# usbhub.net
KiCad netlist of a schematic drawn in Altium Designer
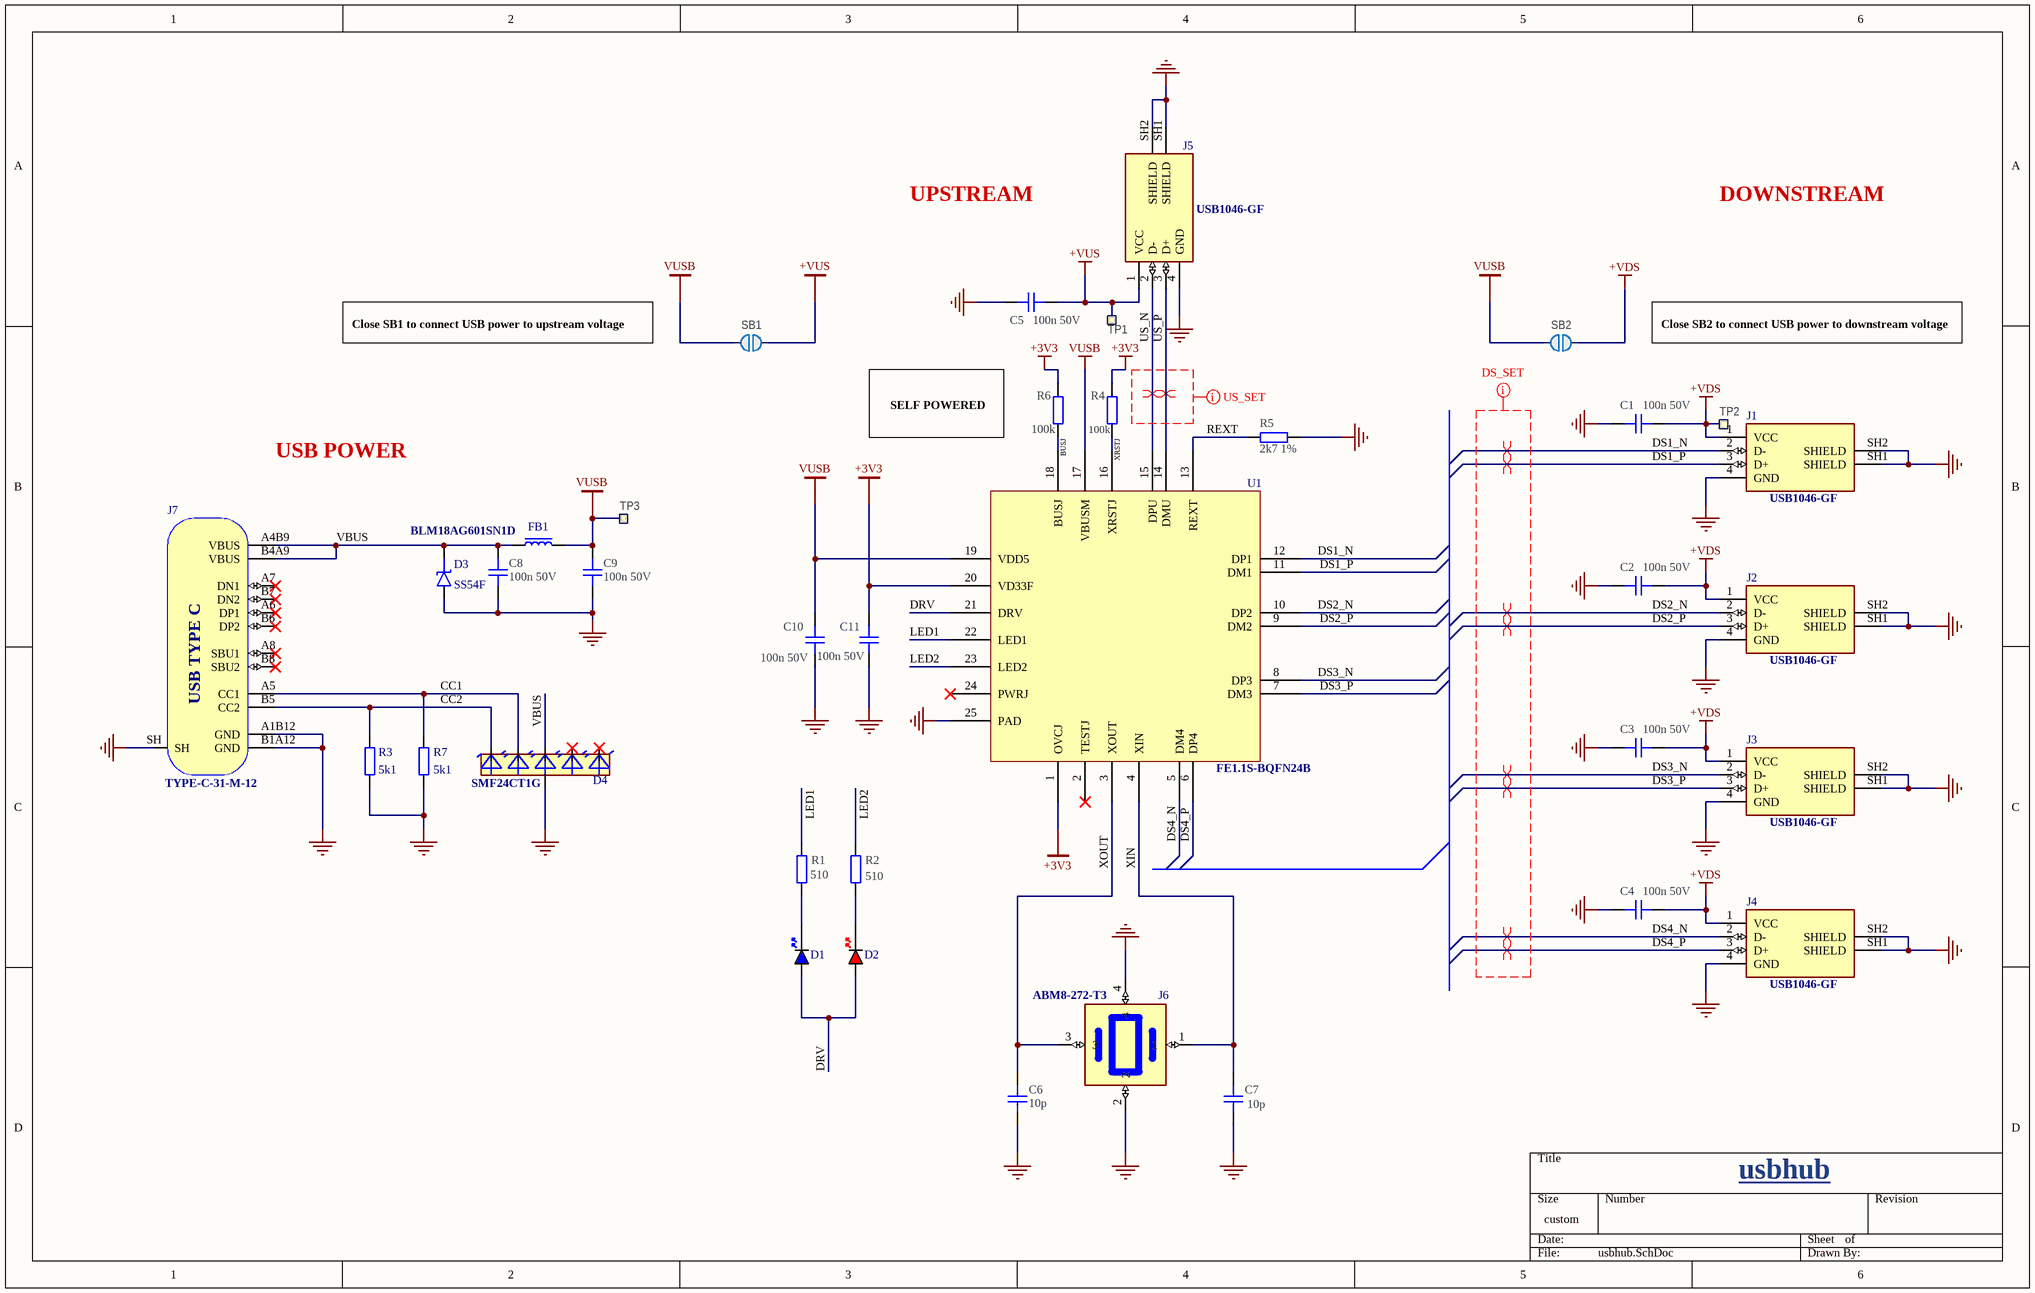
[diagram p0: usbhub.SchDoc]

(export (version "E")
  (design (tool "Eeschema 10.0.6"))
  (components
    (comp (ref "C1")
      (value "100n 50V")
      (footprint "CAPC1005X04L")
      (description "Capacitor, X5R, ±20%")
      (fields
        (field (name "PART NUMBER") "C0402-4µ7")
        (field (name "MANUFACTURER") "N.A.")
        (field (name "AUTHOR") "rsk")
      )
      (libsource (lib "Sch_Lib") (part "C0402-4µ7"))
    )
    (comp (ref "C2")
      (value "100n 50V")
      (footprint "CAPC1005X04L")
      (description "Capacitor, X5R, ±20%")
      (fields
        (field (name "PART NUMBER") "C0402-4µ7")
        (field (name "MANUFACTURER") "N.A.")
        (field (name "AUTHOR") "rsk")
      )
      (libsource (lib "Sch_Lib") (part "C0402-4µ7"))
    )
    (comp (ref "C3")
      (value "100n 50V")
      (footprint "CAPC1005X04L")
      (description "Capacitor, X5R, ±20%")
      (fields
        (field (name "PART NUMBER") "C0402-4µ7")
        (field (name "MANUFACTURER") "N.A.")
        (field (name "AUTHOR") "rsk")
      )
      (libsource (lib "Sch_Lib") (part "C0402-4µ7"))
    )
    (comp (ref "C4")
      (value "100n 50V")
      (footprint "CAPC1005X04L")
      (description "Capacitor, X5R, ±20%")
      (fields
        (field (name "PART NUMBER") "C0402-4µ7")
        (field (name "MANUFACTURER") "N.A.")
        (field (name "AUTHOR") "rsk")
      )
      (libsource (lib "Sch_Lib") (part "C0402-4µ7"))
    )
    (comp (ref "C5")
      (value "100n 50V")
      (footprint "CAPC1005X04L")
      (description "Capacitor, X5R, ±20%")
      (fields
        (field (name "PART NUMBER") "C0402-4µ7")
        (field (name "MANUFACTURER") "N.A.")
        (field (name "AUTHOR") "rsk")
      )
      (libsource (lib "Sch_Lib") (part "C0402-4µ7"))
    )
    (comp (ref "C6")
      (value "10p")
      (footprint "CAPC1005X04L")
      (description "Capacitor, X5R, ±20%")
      (fields
        (field (name "PART NUMBER") "C0402-4µ7")
        (field (name "MANUFACTURER") "N.A.")
        (field (name "AUTHOR") "rsk")
      )
      (libsource (lib "Sch_Lib") (part "C0402-4µ7"))
    )
    (comp (ref "C7")
      (value "10p")
      (footprint "CAPC1005X04L")
      (description "Capacitor, X5R, ±20%")
      (fields
        (field (name "PART NUMBER") "C0402-4µ7")
        (field (name "MANUFACTURER") "N.A.")
        (field (name "AUTHOR") "rsk")
      )
      (libsource (lib "Sch_Lib") (part "C0402-4µ7"))
    )
    (comp (ref "C8")
      (value "100n 50V")
      (footprint "CAPC1005X04L")
      (description "Capacitor, X5R, ±20%")
      (fields
        (field (name "PART NUMBER") "C0402-4µ7")
        (field (name "MANUFACTURER") "N.A.")
        (field (name "AUTHOR") "rsk")
      )
      (libsource (lib "Sch_Lib") (part "C0402-4µ7"))
    )
    (comp (ref "C9")
      (value "100n 50V")
      (footprint "CAPC1005X04L")
      (description "Capacitor, X5R, ±20%")
      (fields
        (field (name "PART NUMBER") "C0402-4µ7")
        (field (name "MANUFACTURER") "N.A.")
        (field (name "AUTHOR") "rsk")
      )
      (libsource (lib "Sch_Lib") (part "C0402-4µ7"))
    )
    (comp (ref "C10")
      (value "100n 50V")
      (footprint "CAPC1005X04L")
      (description "Capacitor, X5R, ±20%")
      (fields
        (field (name "PART NUMBER") "C0402-4µ7")
        (field (name "MANUFACTURER") "N.A.")
        (field (name "AUTHOR") "rsk")
      )
      (libsource (lib "Sch_Lib") (part "C0402-4µ7"))
    )
    (comp (ref "C11")
      (value "100n 50V")
      (footprint "CAPC1005X04L")
      (description "Capacitor, X5R, ±20%")
      (fields
        (field (name "PART NUMBER") "C0402-4µ7")
        (field (name "MANUFACTURER") "N.A.")
        (field (name "AUTHOR") "rsk")
      )
      (libsource (lib "Sch_Lib") (part "C0402-4µ7"))
    )
    (comp (ref "D1")
      (value "BLUE")
      (footprint "LED_0402_BLUE")
      (description "LED 0402 BLUE SMD")
      (libsource (lib "Sch_Lib") (part "LED_0402_BLUE"))
    )
    (comp (ref "D2")
      (value "RED")
      (footprint "LED_0402_RED")
      (description "LED 0402 RED SMD")
      (libsource (lib "Sch_Lib") (part "LED_0402_RED"))
    )
    (comp (ref "D3")
      (value "SS54F")
      (footprint "DIOM5226X100N")
      (description "Schottky Diode SMD SMAF package")
      (libsource (lib "Schematic-Lib-PhilsLab") (part "Schottky Diode_3"))
    )
    (comp (ref "D4")
      (value "SMF24CT1G")
      (footprint "SOT65P210X110-6N")
      (description "Quint Uni-Directional TVS Diode, 100W, 6-Pin SC-88 ¦ ON Semiconductor SMF24CT1G")
      (fields (field (name "MP") "SMF05C") (field (name "MF") "ProTek Devices"))
      (libsource (lib "Sch_Lib") (part "SMF24CT1G"))
    )
    (comp (ref "FB1")
      (value "BLM18AG601SN1D")
      (footprint "FB_0603")
      (description "Ferrite Bead SMD 0603")
      (libsource (lib "Sch_Lib") (part "FB_0603"))
    )
    (comp (ref "J1")
      (value "USB1046-GF")
      (footprint "GCT_USB1046-GF-0190-L-B-A_REVB4")
      (description "USB-A (USB TYPE-A) USB 2.0 Receptacle Connector 4 Position Surface Mount, Through Hole")
      (fields (field (name "MF") "Global Connector Technology") (field (name "MP") "USB1046-GF-0190-L-B-A"))
      (libsource (lib "Sch_Lib") (part "USB1046-GF-0190-L-B-A_REVB4"))
    )
    (comp (ref "J2")
      (value "USB1046-GF")
      (footprint "GCT_USB1046-GF-0190-L-B-A_REVB4")
      (description "USB-A (USB TYPE-A) USB 2.0 Receptacle Connector 4 Position Surface Mount, Through Hole")
      (fields (field (name "MF") "Global Connector Technology") (field (name "MP") "USB1046-GF-0190-L-B-A"))
      (libsource (lib "Sch_Lib") (part "USB1046-GF-0190-L-B-A_REVB4"))
    )
    (comp (ref "J3")
      (value "USB1046-GF")
      (footprint "GCT_USB1046-GF-0190-L-B-A_REVB4")
      (description "USB-A (USB TYPE-A) USB 2.0 Receptacle Connector 4 Position Surface Mount, Through Hole")
      (fields (field (name "MF") "Global Connector Technology") (field (name "MP") "USB1046-GF-0190-L-B-A"))
      (libsource (lib "Sch_Lib") (part "USB1046-GF-0190-L-B-A_REVB4"))
    )
    (comp (ref "J4")
      (value "USB1046-GF")
      (footprint "GCT_USB1046-GF-0190-L-B-A_REVB4")
      (description "USB-A (USB TYPE-A) USB 2.0 Receptacle Connector 4 Position Surface Mount, Through Hole")
      (fields (field (name "MF") "Global Connector Technology") (field (name "MP") "USB1046-GF-0190-L-B-A"))
      (libsource (lib "Sch_Lib") (part "USB1046-GF-0190-L-B-A_REVB4"))
    )
    (comp (ref "J5")
      (value "USB1046-GF")
      (footprint "GCT_USB1046-GF-0190-L-B-A_REVB4")
      (description "USB-A (USB TYPE-A) USB 2.0 Receptacle Connector 4 Position Surface Mount, Through Hole")
      (fields (field (name "MF") "Global Connector Technology") (field (name "MP") "USB1046-GF-0190-L-B-A"))
      (libsource (lib "") (part "USB1046-GF-0190-L-B-A_REVB4_1"))
    )
    (comp (ref "J6")
      (value "ABM8-272-T3")
      (footprint "ABM8-272-T3")
      (description "12 MHz Â±30ppm Crystal 10pF 50 Ohms 4-SMD, No Lead")
      (fields (field (name "MF") "ABRACON"))
      (libsource (lib "Sch_Lib") (part "ABM8-272-T3"))
    )
    (comp (ref "J7")
      (value "TYPE-C-31-M-12")
      (footprint "TYPE-C-31-M-12")
      (description "USB Type C Connector Horizontal SMT")
      (fields (field (name "MANUFACTURER") "Koren Hroparts"))
      (libsource (lib "Sch_Lib") (part "TYPE-C-31-M-12"))
    )
    (comp (ref "R1")
      (value "510")
      (footprint "RESC1005X04L")
      (description "Resistor, ±5%, 0.063W")
      (fields
        (field (name "PART NUMBER") "R0402-0R")
        (field (name "MANUFACTURER") "N.A.")
        (field (name "AUTHOR") "rsk")
      )
      (libsource (lib "Sch_Lib") (part "R0402-0R"))
    )
    (comp (ref "R2")
      (value "510")
      (footprint "RESC1005X04L")
      (description "Resistor, ±5%, 0.063W")
      (fields
        (field (name "PART NUMBER") "R0402-0R")
        (field (name "MANUFACTURER") "N.A.")
        (field (name "AUTHOR") "rsk")
      )
      (libsource (lib "Sch_Lib") (part "R0402-0R"))
    )
    (comp (ref "R3")
      (value "5k1")
      (footprint "RES_0603")
      (description "Resistor SMD 0603")
      (libsource (lib "Schematic-Lib-PhilsLab") (part "RES_0603"))
    )
    (comp (ref "R4")
      (value "100k")
      (footprint "RESC1005X04L")
      (description "Resistor, ±5%, 0.063W")
      (fields
        (field (name "PART NUMBER") "R0402-0R")
        (field (name "MANUFACTURER") "N.A.")
        (field (name "AUTHOR") "rsk")
      )
      (libsource (lib "Sch_Lib") (part "R0402-0R"))
    )
    (comp (ref "R5")
      (value "2k7 1%")
      (footprint "RESC1005X04L")
      (description "Resistor, ±5%, 0.063W")
      (fields
        (field (name "PART NUMBER") "R0402-0R")
        (field (name "MANUFACTURER") "N.A.")
        (field (name "AUTHOR") "rsk")
      )
      (libsource (lib "Sch_Lib") (part "R0402-0R"))
    )
    (comp (ref "R6")
      (value "100k")
      (footprint "RESC1005X04L")
      (description "Resistor, ±5%, 0.063W")
      (fields
        (field (name "PART NUMBER") "R0402-0R")
        (field (name "MANUFACTURER") "N.A.")
        (field (name "AUTHOR") "rsk")
      )
      (libsource (lib "Sch_Lib") (part "R0402-0R"))
    )
    (comp (ref "R7")
      (value "5k1")
      (footprint "RES_0603")
      (description "Resistor SMD 0603")
      (libsource (lib "Schematic-Lib-PhilsLab") (part "RES_0603"))
    )
    (comp (ref "SB1")
      (value "Solderbridge")
      (footprint "Solderbridge")
      (fields (field (name "MANUFACTURER") "N.A.") (field (name "AUTHOR") "rsk"))
      (libsource (lib "Sch_Lib") (part "Solderbridge"))
    )
    (comp (ref "SB2")
      (value "Solderbridge")
      (footprint "Solderbridge")
      (fields (field (name "MANUFACTURER") "N.A.") (field (name "AUTHOR") "rsk"))
      (libsource (lib "Sch_Lib") (part "Solderbridge"))
    )
    (comp (ref "TP1")
      (value "Ø1.0mm,SMD")
      (footprint "TP_SMD_D1.0mm")
      (description "1.0mm circular SMD testpad")
      (fields
        (field (name "PART NUMBER") "TP_SMD_Ø1.0MM")
        (field (name "MANUFACTURER") "Nordic Semiconductor")
        (field (name "AUTHOR") "rsk")
      )
      (libsource (lib "") (part "TP_SMD_Ø1.0MM_1"))
    )
    (comp (ref "TP2")
      (value "Ø1.0mm,SMD")
      (footprint "TP_SMD_D1.0mm")
      (description "1.0mm circular SMD testpad")
      (fields
        (field (name "PART NUMBER") "TP_SMD_Ø1.0MM")
        (field (name "MANUFACTURER") "Nordic Semiconductor")
        (field (name "AUTHOR") "rsk")
      )
      (libsource (lib "Sch_Lib") (part "TP_SMD_Ø1.0MM"))
    )
    (comp (ref "TP3")
      (value "Ø1.0mm,SMD")
      (footprint "TP_SMD_D1.0mm")
      (description "1.0mm circular SMD testpad")
      (fields
        (field (name "PART NUMBER") "TP_SMD_Ø1.0MM")
        (field (name "MANUFACTURER") "Nordic Semiconductor")
        (field (name "AUTHOR") "rsk")
      )
      (libsource (lib "Sch_Lib") (part "TP_SMD_Ø1.0MM"))
    )
    (comp (ref "U1")
      (value "FE1.1S-BQFN24B")
      (footprint "QFN50P400X400X80-25N")
      (description "USB Hub USB 2.0 WQFN-24 Interface Controllers RoHS")
      (libsource (lib "Sch_Lib") (part "FE1.1S-BQFN24B"))
    )
  )
  (nets
    (net (code "1") (name "+3V3") (class "Default")
      (node (ref "C11") (pin "2") (pinfunction "2_2") (pintype "passive"))
      (node (ref "R4") (pin "2") (pinfunction "2_2") (pintype "passive"))
      (node (ref "R6") (pin "2") (pinfunction "2_2") (pintype "passive"))
      (node (ref "U1") (pin "1") (pinfunction "OVCJ_1") (pintype "passive"))
      (node (ref "U1") (pin "20") (pinfunction "VD33F_20") (pintype "passive"))
    )
    (net (code "2") (name "+VDS") (class "Default")
      (node (ref "C1") (pin "2") (pinfunction "2_2") (pintype "passive"))
      (node (ref "C2") (pin "2") (pinfunction "2_2") (pintype "passive"))
      (node (ref "C3") (pin "2") (pinfunction "2_2") (pintype "passive"))
      (node (ref "C4") (pin "2") (pinfunction "2_2") (pintype "passive"))
      (node (ref "J1") (pin "1") (pinfunction "VCC_1") (pintype "power_in"))
      (node (ref "J2") (pin "1") (pinfunction "VCC_1") (pintype "power_in"))
      (node (ref "J3") (pin "1") (pinfunction "VCC_1") (pintype "power_in"))
      (node (ref "J4") (pin "1") (pinfunction "VCC_1") (pintype "power_in"))
      (node (ref "SB2") (pin "1") (pinfunction "0_1") (pintype "passive"))
      (node (ref "TP2") (pin "1") (pinfunction "1_1") (pintype "passive"))
    )
    (net (code "3") (name "+VUS") (class "Default")
      (node (ref "C5") (pin "2") (pinfunction "2_2") (pintype "passive"))
      (node (ref "J5") (pin "1") (pinfunction "VCC_1") (pintype "power_in"))
      (node (ref "SB1") (pin "1") (pinfunction "0_1") (pintype "passive"))
      (node (ref "TP1") (pin "1") (pinfunction "1_1") (pintype "passive"))
    )
    (net (code "4") (name "/BUSJ") (class "Default")
      (node (ref "R6") (pin "1") (pinfunction "1_1") (pintype "passive"))
      (node (ref "U1") (pin "18") (pinfunction "BUSJ_18") (pintype "passive"))
    )
    (net (code "5") (name "/CC1") (class "Default")
      (node (ref "D4") (pin "3") (pinfunction "C2_3") (pintype "passive"))
      (node (ref "J7") (pin "A5") (pinfunction "CC1_A5") (pintype "passive"))
      (node (ref "R7") (pin "2") (pinfunction "2_2") (pintype "passive"))
    )
    (net (code "6") (name "/CC2") (class "Default")
      (node (ref "D4") (pin "1") (pinfunction "C1_1") (pintype "passive"))
      (node (ref "J7") (pin "B5") (pinfunction "CC2_B5") (pintype "tri_state"))
      (node (ref "R3") (pin "2") (pinfunction "2_2") (pintype "passive"))
    )
    (net (code "7") (name "/DRV") (class "Default")
      (node (ref "D1") (pin "A") (pinfunction "A_A") (pintype "passive"))
      (node (ref "D2") (pin "A") (pinfunction "A_A") (pintype "passive"))
      (node (ref "U1") (pin "21") (pinfunction "DRV_21") (pintype "passive"))
    )
    (net (code "8") (name "/DS1_N") (class "Default")
      (node (ref "J1") (pin "2") (pinfunction "D-_2") (pintype "bidirectional"))
      (node (ref "U1") (pin "12") (pinfunction "DP1_12") (pintype "passive"))
    )
    (net (code "9") (name "/DS1_P") (class "Default")
      (node (ref "J1") (pin "3") (pinfunction "D+_3") (pintype "bidirectional"))
      (node (ref "U1") (pin "11") (pinfunction "DM1_11") (pintype "passive"))
    )
    (net (code "10") (name "/DS2_N") (class "Default")
      (node (ref "J2") (pin "2") (pinfunction "D-_2") (pintype "bidirectional"))
      (node (ref "U1") (pin "10") (pinfunction "DP2_10") (pintype "passive"))
    )
    (net (code "11") (name "/DS2_P") (class "Default")
      (node (ref "J2") (pin "3") (pinfunction "D+_3") (pintype "bidirectional"))
      (node (ref "U1") (pin "9") (pinfunction "DM2_9") (pintype "passive"))
    )
    (net (code "12") (name "/DS3_N") (class "Default")
      (node (ref "J3") (pin "2") (pinfunction "D-_2") (pintype "bidirectional"))
      (node (ref "U1") (pin "8") (pinfunction "DP3_8") (pintype "passive"))
    )
    (net (code "13") (name "/DS3_P") (class "Default")
      (node (ref "J3") (pin "3") (pinfunction "D+_3") (pintype "bidirectional"))
      (node (ref "U1") (pin "7") (pinfunction "DM3_7") (pintype "passive"))
    )
    (net (code "14") (name "/DS4_N") (class "Default")
      (node (ref "J4") (pin "2") (pinfunction "D-_2") (pintype "bidirectional"))
      (node (ref "U1") (pin "5") (pinfunction "DM4_5") (pintype "passive"))
    )
    (net (code "15") (name "/DS4_P") (class "Default")
      (node (ref "J4") (pin "3") (pinfunction "D+_3") (pintype "bidirectional"))
      (node (ref "U1") (pin "6") (pinfunction "DP4_6") (pintype "passive"))
    )
    (net (code "16") (name "/LED1") (class "Default")
      (node (ref "R1") (pin "2") (pinfunction "2_2") (pintype "passive"))
      (node (ref "U1") (pin "22") (pinfunction "LED1_22") (pintype "passive"))
    )
    (net (code "17") (name "/LED2") (class "Default")
      (node (ref "R2") (pin "2") (pinfunction "2_2") (pintype "passive"))
      (node (ref "U1") (pin "23") (pinfunction "LED2_23") (pintype "passive"))
    )
    (net (code "18") (name "/REXT") (class "Default")
      (node (ref "R5") (pin "1") (pinfunction "1_1") (pintype "passive"))
      (node (ref "U1") (pin "13") (pinfunction "REXT_13") (pintype "passive"))
    )
    (net (code "19") (name "/US_N") (class "Default")
      (node (ref "J5") (pin "2") (pinfunction "D-_2") (pintype "bidirectional"))
      (node (ref "U1") (pin "15") (pinfunction "DPU_15") (pintype "passive"))
    )
    (net (code "20") (name "/US_P") (class "Default")
      (node (ref "J5") (pin "3") (pinfunction "D+_3") (pintype "bidirectional"))
      (node (ref "U1") (pin "14") (pinfunction "DMU_14") (pintype "passive"))
    )
    (net (code "21") (name "/VBUS") (class "Default")
      (node (ref "C8") (pin "1") (pinfunction "1_1") (pintype "passive"))
      (node (ref "D3") (pin "K") (pinfunction "K_K") (pintype "passive"))
      (node (ref "D4") (pin "4") (pinfunction "C3_4") (pintype "passive"))
      (node (ref "FB1") (pin "2") (pinfunction "2_2") (pintype "passive"))
      (node (ref "J7") (pin "A4B9") (pinfunction "VBUS_A4B9") (pintype "power_in"))
      (node (ref "J7") (pin "B4A9") (pinfunction "VBUS_B4A9") (pintype "power_in"))
    )
    (net (code "22") (name "/XIN") (class "Default")
      (node (ref "C7") (pin "2") (pinfunction "2_2") (pintype "passive"))
      (node (ref "J6") (pin "1") (pinfunction "1_1") (pintype "bidirectional"))
      (node (ref "U1") (pin "4") (pinfunction "XIN_4") (pintype "passive"))
    )
    (net (code "23") (name "/XOUT") (class "Default")
      (node (ref "C6") (pin "2") (pinfunction "2_2") (pintype "passive"))
      (node (ref "J6") (pin "3") (pinfunction "3_3") (pintype "bidirectional"))
      (node (ref "U1") (pin "3") (pinfunction "XOUT_3") (pintype "passive"))
    )
    (net (code "24") (name "/XRSTJ") (class "Default")
      (node (ref "R4") (pin "1") (pinfunction "1_1") (pintype "passive"))
      (node (ref "U1") (pin "16") (pinfunction "XRSTJ_16") (pintype "passive"))
    )
    (net (code "25") (name "GND") (class "Default")
      (node (ref "C1") (pin "1") (pinfunction "1_1") (pintype "passive"))
      (node (ref "C10") (pin "1") (pinfunction "1_1") (pintype "passive"))
      (node (ref "C11") (pin "1") (pinfunction "1_1") (pintype "passive"))
      (node (ref "C2") (pin "1") (pinfunction "1_1") (pintype "passive"))
      (node (ref "C3") (pin "1") (pinfunction "1_1") (pintype "passive"))
      (node (ref "C4") (pin "1") (pinfunction "1_1") (pintype "passive"))
      (node (ref "C5") (pin "1") (pinfunction "1_1") (pintype "passive"))
      (node (ref "C6") (pin "1") (pinfunction "1_1") (pintype "passive"))
      (node (ref "C7") (pin "1") (pinfunction "1_1") (pintype "passive"))
      (node (ref "C8") (pin "2") (pinfunction "2_2") (pintype "passive"))
      (node (ref "C9") (pin "2") (pinfunction "2_2") (pintype "passive"))
      (node (ref "D3") (pin "A") (pinfunction "A_A") (pintype "passive"))
      (node (ref "D4") (pin "2") (pinfunction "A_2") (pintype "passive"))
      (node (ref "J1") (pin "4") (pinfunction "GND_4") (pintype "power_in"))
      (node (ref "J1") (pin "SH1") (pinfunction "SHIELD_SH1") (pintype "passive"))
      (node (ref "J1") (pin "SH2") (pinfunction "SHIELD_SH2") (pintype "passive"))
      (node (ref "J2") (pin "4") (pinfunction "GND_4") (pintype "power_in"))
      (node (ref "J2") (pin "SH1") (pinfunction "SHIELD_SH1") (pintype "passive"))
      (node (ref "J2") (pin "SH2") (pinfunction "SHIELD_SH2") (pintype "passive"))
      (node (ref "J3") (pin "4") (pinfunction "GND_4") (pintype "power_in"))
      (node (ref "J3") (pin "SH1") (pinfunction "SHIELD_SH1") (pintype "passive"))
      (node (ref "J3") (pin "SH2") (pinfunction "SHIELD_SH2") (pintype "passive"))
      (node (ref "J4") (pin "4") (pinfunction "GND_4") (pintype "power_in"))
      (node (ref "J4") (pin "SH1") (pinfunction "SHIELD_SH1") (pintype "passive"))
      (node (ref "J4") (pin "SH2") (pinfunction "SHIELD_SH2") (pintype "passive"))
      (node (ref "J5") (pin "4") (pinfunction "GND_4") (pintype "power_in"))
      (node (ref "J5") (pin "SH1") (pinfunction "SHIELD_SH1") (pintype "passive"))
      (node (ref "J5") (pin "SH2") (pinfunction "SHIELD_SH2") (pintype "passive"))
      (node (ref "J6") (pin "2") (pinfunction "2_2") (pintype "bidirectional"))
      (node (ref "J6") (pin "4") (pinfunction "4_4") (pintype "bidirectional"))
      (node (ref "J7") (pin "A1B12") (pinfunction "GND_A1B12") (pintype "power_in"))
      (node (ref "J7") (pin "B1A12") (pinfunction "GND_B1A12") (pintype "power_in"))
      (node (ref "J7") (pin "SH") (pinfunction "SH_SH") (pintype "power_in"))
      (node (ref "R3") (pin "1") (pinfunction "1_1") (pintype "passive"))
      (node (ref "R5") (pin "2") (pinfunction "2_2") (pintype "passive"))
      (node (ref "R7") (pin "1") (pinfunction "1_1") (pintype "passive"))
      (node (ref "U1") (pin "25") (pinfunction "PAD_25") (pintype "passive"))
    )
    (net (code "26") (name "Net-(D1-PadK)") (class "Default")
      (node (ref "D1") (pin "K") (pinfunction "K_K") (pintype "passive"))
      (node (ref "R1") (pin "1") (pinfunction "1_1") (pintype "passive"))
    )
    (net (code "27") (name "Net-(D2-PadK)") (class "Default")
      (node (ref "D2") (pin "K") (pinfunction "K_K") (pintype "passive"))
      (node (ref "R2") (pin "1") (pinfunction "1_1") (pintype "passive"))
    )
    (net (code "28") (name "VUSB") (class "Default")
      (node (ref "C10") (pin "2") (pinfunction "2_2") (pintype "passive"))
      (node (ref "C9") (pin "1") (pinfunction "1_1") (pintype "passive"))
      (node (ref "FB1") (pin "1") (pinfunction "1_1") (pintype "passive"))
      (node (ref "SB1") (pin "2") (pinfunction "1_2") (pintype "passive"))
      (node (ref "SB2") (pin "2") (pinfunction "1_2") (pintype "passive"))
      (node (ref "TP3") (pin "1") (pinfunction "1_1") (pintype "passive"))
      (node (ref "U1") (pin "17") (pinfunction "VBUSM_17") (pintype "passive"))
      (node (ref "U1") (pin "19") (pinfunction "VDD5_19") (pintype "passive"))
    )
    (net (code "29") (name "unconnected-(D4-C4-Pad5)") (class "Default")
      (node (ref "D4") (pin "5") (pinfunction "C4_5") (pintype "passive+no_connect"))
    )
    (net (code "30") (name "unconnected-(D4-C5-Pad6)") (class "Default")
      (node (ref "D4") (pin "6") (pinfunction "C5_6") (pintype "passive+no_connect"))
    )
    (net (code "31") (name "unconnected-(J7-DN1-PadA7)") (class "Default")
      (node (ref "J7") (pin "A7") (pinfunction "DN1_A7") (pintype "bidirectional+no_connect"))
    )
    (net (code "32") (name "unconnected-(J7-DN2-PadB7)") (class "Default")
      (node (ref "J7") (pin "B7") (pinfunction "DN2_B7") (pintype "bidirectional+no_connect"))
    )
    (net (code "33") (name "unconnected-(J7-DP1-PadA6)") (class "Default")
      (node (ref "J7") (pin "A6") (pinfunction "DP1_A6") (pintype "bidirectional+no_connect"))
    )
    (net (code "34") (name "unconnected-(J7-DP2-PadB6)") (class "Default")
      (node (ref "J7") (pin "B6") (pinfunction "DP2_B6") (pintype "bidirectional+no_connect"))
    )
    (net (code "35") (name "unconnected-(J7-SBU1-PadA8)") (class "Default")
      (node (ref "J7") (pin "A8") (pinfunction "SBU1_A8") (pintype "bidirectional+no_connect"))
    )
    (net (code "36") (name "unconnected-(J7-SBU2-PadB8)") (class "Default")
      (node (ref "J7") (pin "B8") (pinfunction "SBU2_B8") (pintype "bidirectional+no_connect"))
    )
    (net (code "37") (name "unconnected-(U1-PWRJ-Pad24)") (class "Default")
      (node (ref "U1") (pin "24") (pinfunction "PWRJ_24") (pintype "passive+no_connect"))
    )
    (net (code "38") (name "unconnected-(U1-TESTJ-Pad2)") (class "Default")
      (node (ref "U1") (pin "2") (pinfunction "TESTJ_2") (pintype "passive+no_connect"))
    )
  )
)
